# RK3566_OSC_PLL_PMUO1_2.net
KiCad netlist of a schematic drawn in Altium Designer
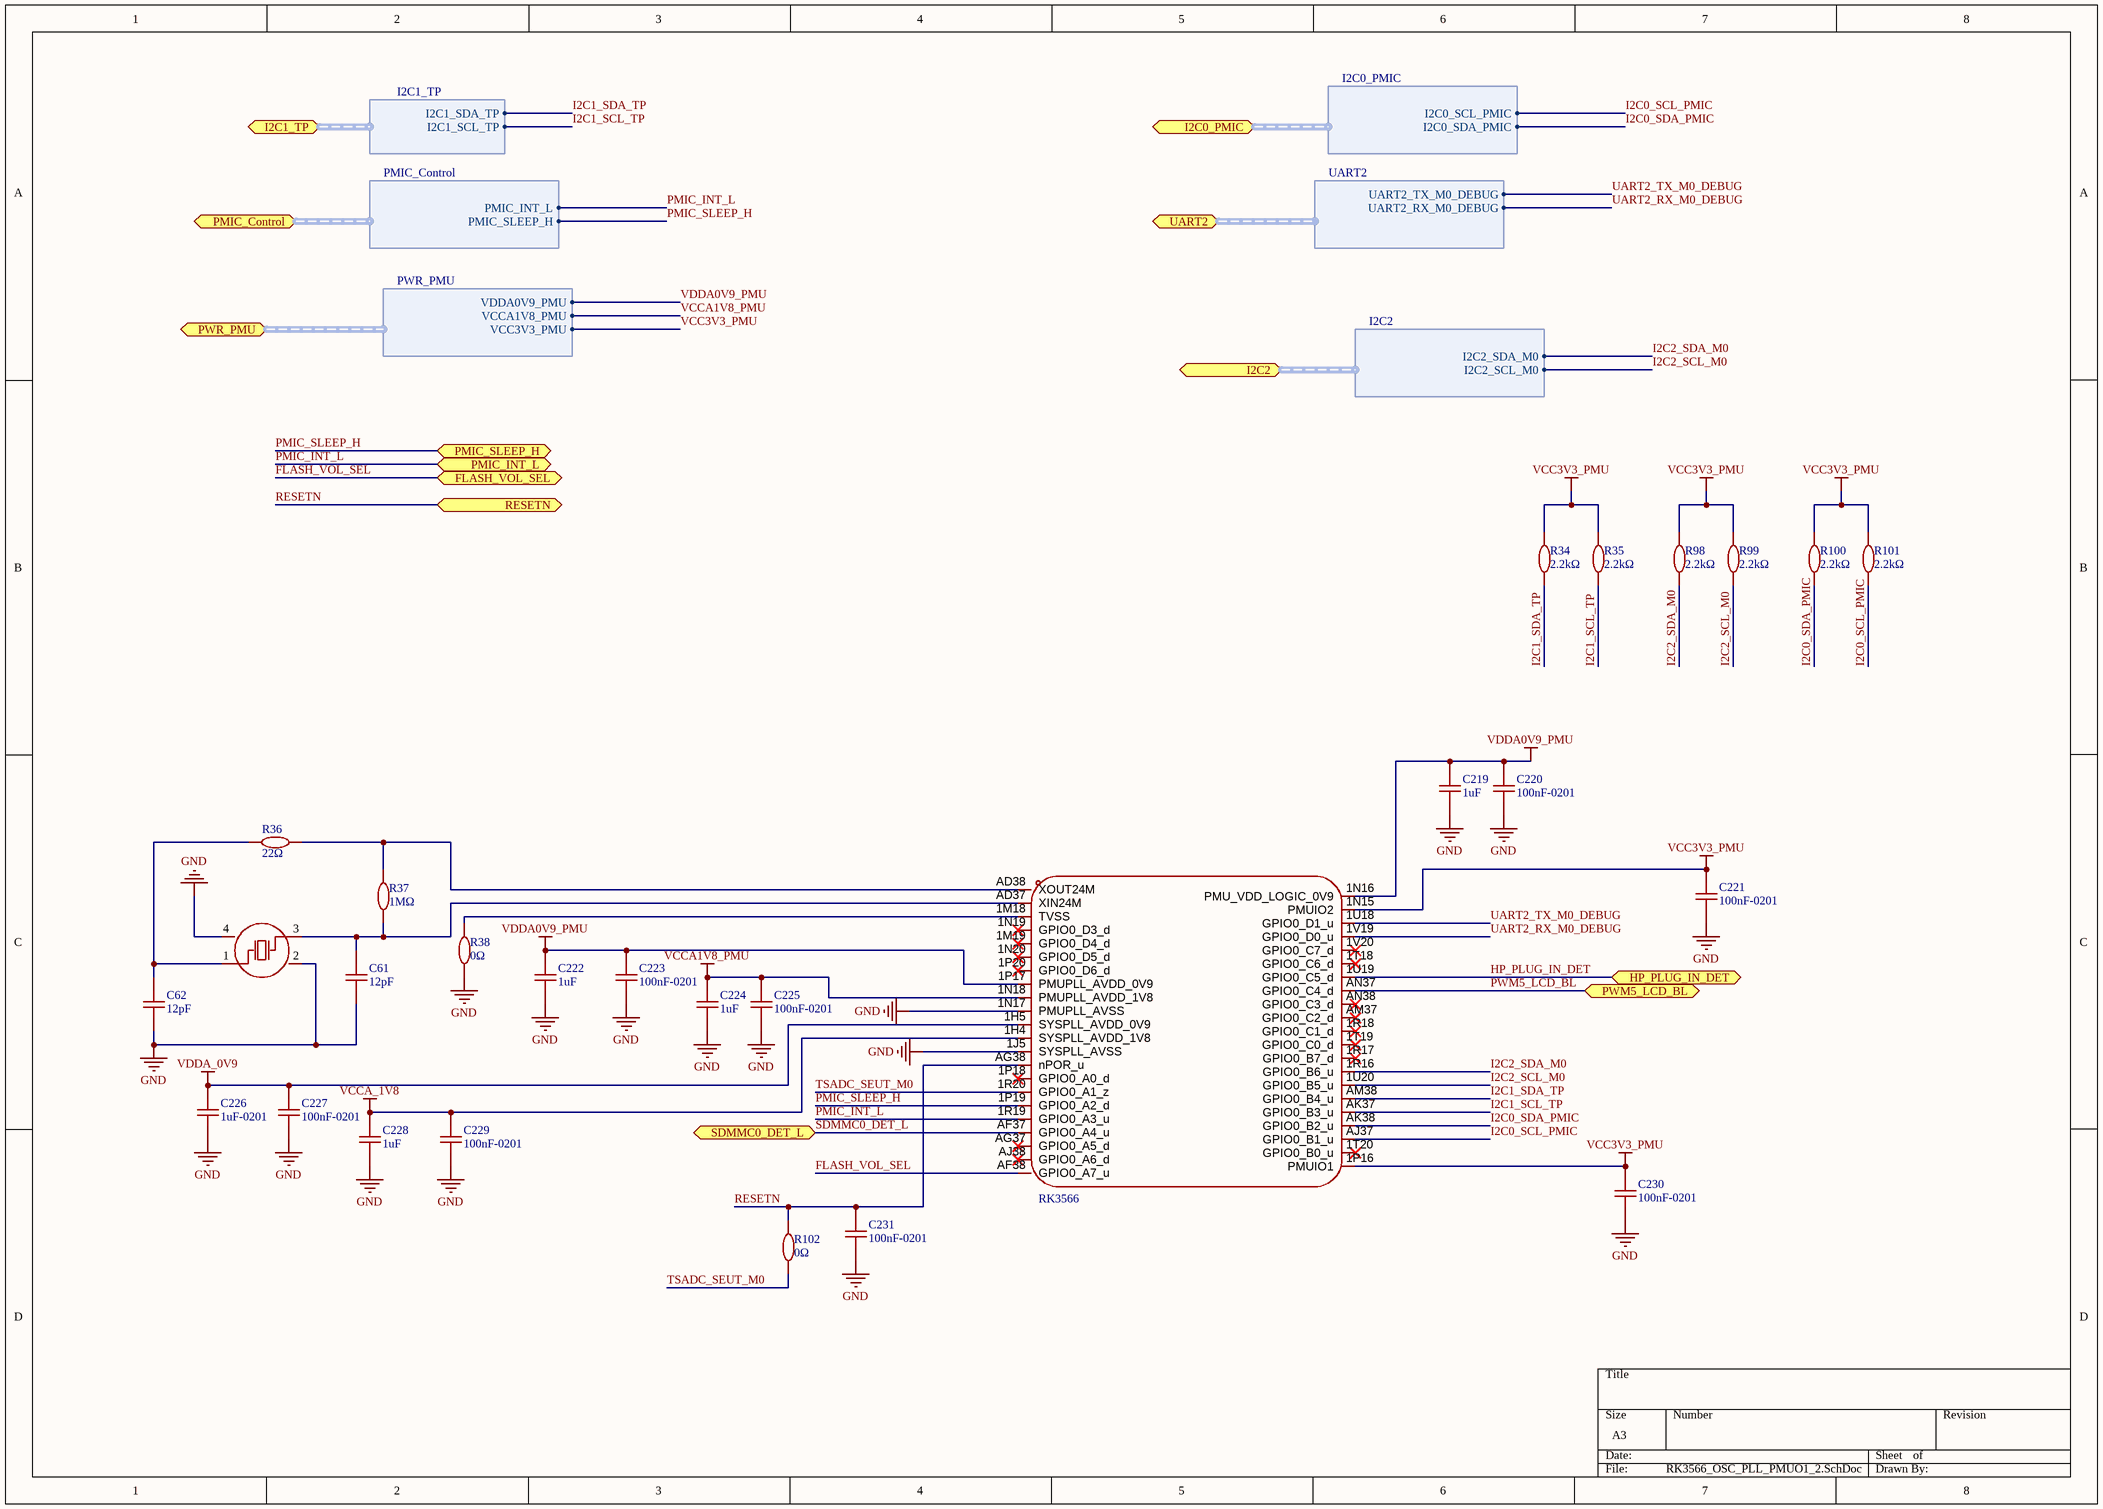
[diagram p0: RK3566_OSC_PLL_PMUO1_2.SchDoc]

(export (version "E")
  (design (tool "Eeschema 10.0.6"))
  (components
    (comp (ref "C61")
      (value "12pF")
      (footprint "C0402")
      (description "50V 12pF C0G ±5% 0402 Ceramic Capacitors ROHS")
      (libsource (lib "RLC") (part "12pF"))
    )
    (comp (ref "C62")
      (value "12pF")
      (footprint "C0402")
      (description "50V 12pF C0G ±5% 0402 Ceramic Capacitors ROHS")
      (libsource (lib "RLC") (part "12pF"))
    )
    (comp (ref "C219")
      (value "1uF")
      (footprint "C0402")
      (description "50V 1uF X5R ±10% 0402 Ceramic Capacitors ROHS")
      (libsource (lib "RLC") (part "1uF"))
    )
    (comp (ref "C220")
      (value "100nF-0201")
      (footprint "C0201")
      (description "CL03A104KO3NNNC")
      (libsource (lib "RLC") (part "100nF-0201"))
    )
    (comp (ref "C221")
      (value "100nF-0201")
      (footprint "C0201")
      (description "CL03A104KO3NNNC")
      (libsource (lib "RLC") (part "100nF-0201"))
    )
    (comp (ref "C222")
      (value "1uF")
      (footprint "C0402")
      (description "50V 1uF X5R ±10% 0402 Ceramic Capacitors ROHS")
      (libsource (lib "RLC") (part "1uF"))
    )
    (comp (ref "C223")
      (value "100nF-0201")
      (footprint "C0201")
      (description "CL03A104KO3NNNC")
      (libsource (lib "RLC") (part "100nF-0201"))
    )
    (comp (ref "C224")
      (value "1uF")
      (footprint "C0402")
      (description "50V 1uF X5R ±10% 0402 Ceramic Capacitors ROHS")
      (libsource (lib "RLC") (part "1uF"))
    )
    (comp (ref "C225")
      (value "100nF-0201")
      (footprint "C0201")
      (description "CL03A104KO3NNNC")
      (libsource (lib "RLC") (part "100nF-0201"))
    )
    (comp (ref "C226")
      (value "1uF-0201")
      (footprint "C0201")
      (description "CL03A104KO3NNNC")
      (libsource (lib "RLC") (part "1uF-0201"))
    )
    (comp (ref "C227")
      (value "100nF-0201")
      (footprint "C0201")
      (description "CL03A104KO3NNNC")
      (libsource (lib "RLC") (part "100nF-0201"))
    )
    (comp (ref "C228")
      (value "1uF")
      (footprint "C0402")
      (description "50V 1uF X5R ±10% 0402 Ceramic Capacitors ROHS")
      (libsource (lib "RLC") (part "1uF"))
    )
    (comp (ref "C229")
      (value "100nF-0201")
      (footprint "C0201")
      (description "CL03A104KO3NNNC")
      (libsource (lib "RLC") (part "100nF-0201"))
    )
    (comp (ref "C230")
      (value "100nF-0201")
      (footprint "C0201")
      (description "CL03A104KO3NNNC")
      (libsource (lib "RLC") (part "100nF-0201"))
    )
    (comp (ref "C231")
      (value "100nF-0201")
      (footprint "C0201")
      (description "CL03A104KO3NNNC")
      (libsource (lib "RLC") (part "100nF-0201"))
    )
    (comp (ref "R34")
      (value "2.2kΩ")
      (footprint "R0402")
      (description "2.2kΩ ±1% 62.5mW 厚膜电阻")
      (libsource (lib "RLC") (part "2.2kΩ"))
    )
    (comp (ref "R35")
      (value "2.2kΩ")
      (footprint "R0402")
      (description "2.2kΩ ±1% 62.5mW 厚膜电阻")
      (libsource (lib "RLC") (part "2.2kΩ"))
    )
    (comp (ref "R36")
      (value "22Ω")
      (footprint "R0402")
      (description "小尺寸、重量轻。降低组装成本,与贴片机匹配。适用于波峰焊和回流焊")
      (libsource (lib "RLC") (part "22Ω"))
    )
    (comp (ref "R37")
      (value "1MΩ")
      (footprint "R0402")
      (description "62.5mW 1MΩ 50V ±100ppm/℃ Thick Film Resistor ±1% 0402 Chip Resistor - Surface Mount ROHS")
      (libsource (lib "RLC") (part "1MΩ"))
    )
    (comp (ref "R38")
      (value "0Ω")
      (footprint "R0402")
      (description "小尺寸、重量轻。降低组装成本,与贴片机匹配。适用于波峰焊和回流焊")
      (libsource (lib "RLC") (part "0Ω-0201"))
    )
    (comp (ref "R98")
      (value "2.2kΩ")
      (footprint "R0402")
      (description "2.2kΩ ±1% 62.5mW 厚膜电阻")
      (libsource (lib "RLC") (part "2.2kΩ"))
    )
    (comp (ref "R99")
      (value "2.2kΩ")
      (footprint "R0402")
      (description "2.2kΩ ±1% 62.5mW 厚膜电阻")
      (libsource (lib "RLC") (part "2.2kΩ"))
    )
    (comp (ref "R100")
      (value "2.2kΩ")
      (footprint "R0402")
      (description "2.2kΩ ±1% 62.5mW 厚膜电阻")
      (libsource (lib "RLC") (part "2.2kΩ"))
    )
    (comp (ref "R101")
      (value "2.2kΩ")
      (footprint "R0402")
      (description "2.2kΩ ±1% 62.5mW 厚膜电阻")
      (libsource (lib "RLC") (part "2.2kΩ"))
    )
    (comp (ref "R102")
      (value "0Ω")
      (footprint "R0402")
      (description "0Ω 62.5mW 50V Thick Film Resistor ±1% 0402 Chip Resistor - Surface Mount ROHS")
      (libsource (lib "RLC") (part "0Ω"))
    )
    (comp (ref "U2")
      (value "RK3566")
      (footprint "BGA-565_L15.5-W14.4-P0.40_RK3566_1")
      (description "BGA-565(15.5x14.4)")
      (libsource (lib "IC") (part "RK3566"))
    )
    (comp (ref "X2")
      (value "24MHz")
      (footprint "CRYSTAL-SMD_4P-L3.2-W2.5-BL")
      (description "Crystal Oscillator 12pF SMD3225-4P Crystals ROHS")
      (fields (field (name "MANUFACTURER") "YXC(扬兴晶振)") (field (name "MANUFACTURER PART") "X322524MOB4SI"))
      (libsource (lib "OSC") (part "X322524MOB4SI"))
    )
  )
  (nets
    (net (code "7") (name "/FLASH_VOL_SEL") (class "Default")
      (node (ref "U2") (pin "AF38") (pinfunction "GPIO0_A7_u_AF38") (pintype "passive"))
    )
    (net (code "8") (name "/HP_PLUG_IN_DET") (class "Default")
      (node (ref "U2") (pin "1U19") (pinfunction "GPIO0_C5_d_1U19") (pintype "passive"))
    )
    (net (code "9") (name "/I2C0_SCL_PMIC") (class "Default")
      (node (ref "R101") (pin "1") (pinfunction "1_1") (pintype "passive"))
      (node (ref "U2") (pin "AJ37") (pinfunction "GPIO0_B1_u_AJ37") (pintype "passive"))
    )
    (net (code "10") (name "/I2C0_SDA_PMIC") (class "Default")
      (node (ref "R100") (pin "1") (pinfunction "1_1") (pintype "passive"))
      (node (ref "U2") (pin "AK38") (pinfunction "GPIO0_B2_u_AK38") (pintype "passive"))
    )
    (net (code "11") (name "/I2C1_SCL_TP") (class "Default")
      (node (ref "R35") (pin "1") (pinfunction "1_1") (pintype "passive"))
      (node (ref "U2") (pin "AK37") (pinfunction "GPIO0_B3_u_AK37") (pintype "passive"))
    )
    (net (code "12") (name "/I2C1_SDA_TP") (class "Default")
      (node (ref "R34") (pin "1") (pinfunction "1_1") (pintype "passive"))
      (node (ref "U2") (pin "AM38") (pinfunction "GPIO0_B4_u_AM38") (pintype "passive"))
    )
    (net (code "13") (name "/I2C2_SCL_M0") (class "Default")
      (node (ref "R99") (pin "1") (pinfunction "1_1") (pintype "passive"))
      (node (ref "U2") (pin "1U20") (pinfunction "GPIO0_B5_u_1U20") (pintype "passive"))
    )
    (net (code "14") (name "/I2C2_SDA_M0") (class "Default")
      (node (ref "R98") (pin "1") (pinfunction "1_1") (pintype "passive"))
      (node (ref "U2") (pin "1R16") (pinfunction "GPIO0_B6_u_1R16") (pintype "passive"))
    )
    (net (code "15") (name "/PMIC_INT_L") (class "Default")
      (node (ref "U2") (pin "1R19") (pinfunction "GPIO0_A3_u_1R19") (pintype "passive"))
    )
    (net (code "16") (name "/PMIC_SLEEP_H") (class "Default")
      (node (ref "U2") (pin "1P19") (pinfunction "GPIO0_A2_d_1P19") (pintype "passive"))
    )
    (net (code "17") (name "/PWM5_LCD_BL") (class "Default")
      (node (ref "U2") (pin "AN37") (pinfunction "GPIO0_C4_d_AN37") (pintype "passive"))
    )
    (net (code "18") (name "/RESETN") (class "Default")
      (node (ref "C231") (pin "2") (pinfunction "2_2") (pintype "passive"))
      (node (ref "R102") (pin "2") (pinfunction "2_2") (pintype "passive"))
      (node (ref "U2") (pin "AG38") (pinfunction "nPOR_u_AG38") (pintype "passive"))
    )
    (net (code "19") (name "/SDMMC0_DET_L") (class "Default")
      (node (ref "U2") (pin "AF37") (pinfunction "GPIO0_A4_u_AF37") (pintype "passive"))
    )
    (net (code "20") (name "/TSADC_SEUT_M0") (class "Default")
      (node (ref "R102") (pin "1") (pinfunction "1_1") (pintype "passive"))
      (node (ref "U2") (pin "1R20") (pinfunction "GPIO0_A1_z_1R20") (pintype "passive"))
    )
    (net (code "21") (name "/UART2_RX_M0_DEBUG") (class "Default")
      (node (ref "U2") (pin "1V19") (pinfunction "GPIO0_D0_u_1V19") (pintype "passive"))
    )
    (net (code "22") (name "/UART2_TX_M0_DEBUG") (class "Default")
      (node (ref "U2") (pin "1U18") (pinfunction "GPIO0_D1_u_1U18") (pintype "passive"))
    )
    (net (code "29") (name "GND") (class "Default")
      (node (ref "C219") (pin "1") (pinfunction "1_1") (pintype "passive"))
      (node (ref "C220") (pin "1") (pinfunction "1_1") (pintype "passive"))
      (node (ref "C221") (pin "1") (pinfunction "1_1") (pintype "passive"))
      (node (ref "C222") (pin "1") (pinfunction "1_1") (pintype "passive"))
      (node (ref "C223") (pin "1") (pinfunction "1_1") (pintype "passive"))
      (node (ref "C224") (pin "1") (pinfunction "1_1") (pintype "passive"))
      (node (ref "C225") (pin "1") (pinfunction "1_1") (pintype "passive"))
      (node (ref "C226") (pin "1") (pinfunction "1_1") (pintype "passive"))
      (node (ref "C227") (pin "1") (pinfunction "1_1") (pintype "passive"))
      (node (ref "C228") (pin "1") (pinfunction "1_1") (pintype "passive"))
      (node (ref "C229") (pin "1") (pinfunction "1_1") (pintype "passive"))
      (node (ref "C230") (pin "1") (pinfunction "1_1") (pintype "passive"))
      (node (ref "C231") (pin "1") (pinfunction "1_1") (pintype "passive"))
      (node (ref "C61") (pin "1") (pinfunction "1_1") (pintype "passive"))
      (node (ref "C62") (pin "1") (pinfunction "1_1") (pintype "passive"))
      (node (ref "R38") (pin "1") (pinfunction "1_1") (pintype "passive"))
      (node (ref "U2") (pin "1J5") (pinfunction "SYSPLL_AVSS_1J5") (pintype "passive"))
      (node (ref "U2") (pin "1N17") (pinfunction "PMUPLL_AVSS_1N17") (pintype "passive"))
      (node (ref "X2") (pin "2") (pinfunction "GND_2") (pintype "passive"))
      (node (ref "X2") (pin "4") (pinfunction "GND_4") (pintype "passive"))
    )
    (net (code "30") (name "Net-(U2D-TVSS)") (class "Default")
      (node (ref "R38") (pin "2") (pinfunction "2_2") (pintype "passive"))
      (node (ref "U2") (pin "1M18") (pinfunction "TVSS_1M18") (pintype "passive"))
    )
    (net (code "31") (name "Net-(U2D-XIN24M)") (class "Default")
      (node (ref "C61") (pin "2") (pinfunction "2_2") (pintype "passive"))
      (node (ref "R37") (pin "1") (pinfunction "1_1") (pintype "passive"))
      (node (ref "U2") (pin "AD37") (pinfunction "XIN24M_AD37") (pintype "passive"))
      (node (ref "X2") (pin "3") (pinfunction "OSC2_3") (pintype "passive"))
    )
    (net (code "32") (name "Net-(U2D-XOUT24M)") (class "Default")
      (node (ref "R36") (pin "2") (pinfunction "2_2") (pintype "passive"))
      (node (ref "R37") (pin "2") (pinfunction "2_2") (pintype "passive"))
      (node (ref "U2") (pin "AD38") (pinfunction "XOUT24M_AD38") (pintype "passive"))
    )
    (net (code "33") (name "Net-(X2-OSC1)") (class "Default")
      (node (ref "C62") (pin "2") (pinfunction "2_2") (pintype "passive"))
      (node (ref "R36") (pin "1") (pinfunction "1_1") (pintype "passive"))
      (node (ref "X2") (pin "1") (pinfunction "OSC1_1") (pintype "passive"))
    )
    (net (code "34") (name "VCC3V3_PMU") (class "Default")
      (node (ref "C221") (pin "2") (pinfunction "2_2") (pintype "passive"))
      (node (ref "C230") (pin "2") (pinfunction "2_2") (pintype "passive"))
      (node (ref "R100") (pin "2") (pinfunction "2_2") (pintype "passive"))
      (node (ref "R101") (pin "2") (pinfunction "2_2") (pintype "passive"))
      (node (ref "R34") (pin "2") (pinfunction "2_2") (pintype "passive"))
      (node (ref "R35") (pin "2") (pinfunction "2_2") (pintype "passive"))
      (node (ref "R98") (pin "2") (pinfunction "2_2") (pintype "passive"))
      (node (ref "R99") (pin "2") (pinfunction "2_2") (pintype "passive"))
      (node (ref "U2") (pin "1N15") (pinfunction "PMUIO2_1N15") (pintype "passive"))
      (node (ref "U2") (pin "1P16") (pinfunction "PMUIO1_1P16") (pintype "passive"))
    )
    (net (code "35") (name "VCCA1V8_PMU") (class "Default")
      (node (ref "C224") (pin "2") (pinfunction "2_2") (pintype "passive"))
      (node (ref "C225") (pin "2") (pinfunction "2_2") (pintype "passive"))
      (node (ref "U2") (pin "1N18") (pinfunction "PMUPLL_AVDD_1V8_1N18") (pintype "passive"))
    )
    (net (code "36") (name "VCCA_1V8") (class "Default")
      (node (ref "C228") (pin "2") (pinfunction "2_2") (pintype "passive"))
      (node (ref "C229") (pin "2") (pinfunction "2_2") (pintype "passive"))
      (node (ref "U2") (pin "1H4") (pinfunction "SYSPLL_AVDD_1V8_1H4") (pintype "passive"))
    )
    (net (code "37") (name "VDDA0V9_PMU") (class "Default")
      (node (ref "C219") (pin "2") (pinfunction "2_2") (pintype "passive"))
      (node (ref "C220") (pin "2") (pinfunction "2_2") (pintype "passive"))
      (node (ref "C222") (pin "2") (pinfunction "2_2") (pintype "passive"))
      (node (ref "C223") (pin "2") (pinfunction "2_2") (pintype "passive"))
      (node (ref "U2") (pin "1N16") (pinfunction "PMU_VDD_LOGIC_0V9_1N16") (pintype "passive"))
      (node (ref "U2") (pin "1P17") (pinfunction "PMUPLL_AVDD_0V9_1P17") (pintype "passive"))
    )
    (net (code "38") (name "VDDA_0V9") (class "Default")
      (node (ref "C226") (pin "2") (pinfunction "2_2") (pintype "passive"))
      (node (ref "C227") (pin "2") (pinfunction "2_2") (pintype "passive"))
      (node (ref "U2") (pin "1H5") (pinfunction "SYSPLL_AVDD_0V9_1H5") (pintype "passive"))
    )
    (net (code "39") (name "unconnected-(U2D-GPIO0_A0_d-Pad1P18)") (class "Default")
      (node (ref "U2") (pin "1P18") (pinfunction "GPIO0_A0_d_1P18") (pintype "passive+no_connect"))
    )
    (net (code "40") (name "unconnected-(U2D-GPIO0_A5_d-PadAG37)") (class "Default")
      (node (ref "U2") (pin "AG37") (pinfunction "GPIO0_A5_d_AG37") (pintype "passive+no_connect"))
    )
    (net (code "41") (name "unconnected-(U2D-GPIO0_A6_d-PadAJ38)") (class "Default")
      (node (ref "U2") (pin "AJ38") (pinfunction "GPIO0_A6_d_AJ38") (pintype "passive+no_connect"))
    )
    (net (code "42") (name "unconnected-(U2D-GPIO0_B0_u-Pad1T20)") (class "Default")
      (node (ref "U2") (pin "1T20") (pinfunction "GPIO0_B0_u_1T20") (pintype "passive+no_connect"))
    )
    (net (code "43") (name "unconnected-(U2D-GPIO0_B7_d-Pad1R17)") (class "Default")
      (node (ref "U2") (pin "1R17") (pinfunction "GPIO0_B7_d_1R17") (pintype "passive+no_connect"))
    )
    (net (code "44") (name "unconnected-(U2D-GPIO0_C0_d-Pad1T19)") (class "Default")
      (node (ref "U2") (pin "1T19") (pinfunction "GPIO0_C0_d_1T19") (pintype "passive+no_connect"))
    )
    (net (code "45") (name "unconnected-(U2D-GPIO0_C1_d-Pad1R18)") (class "Default")
      (node (ref "U2") (pin "1R18") (pinfunction "GPIO0_C1_d_1R18") (pintype "passive+no_connect"))
    )
    (net (code "46") (name "unconnected-(U2D-GPIO0_C2_d-PadAM37)") (class "Default")
      (node (ref "U2") (pin "AM37") (pinfunction "GPIO0_C2_d_AM37") (pintype "passive+no_connect"))
    )
    (net (code "47") (name "unconnected-(U2D-GPIO0_C3_d-PadAN38)") (class "Default")
      (node (ref "U2") (pin "AN38") (pinfunction "GPIO0_C3_d_AN38") (pintype "passive+no_connect"))
    )
    (net (code "48") (name "unconnected-(U2D-GPIO0_C6_d-Pad1T18)") (class "Default")
      (node (ref "U2") (pin "1T18") (pinfunction "GPIO0_C6_d_1T18") (pintype "passive+no_connect"))
    )
    (net (code "49") (name "unconnected-(U2D-GPIO0_C7_d-Pad1V20)") (class "Default")
      (node (ref "U2") (pin "1V20") (pinfunction "GPIO0_C7_d_1V20") (pintype "passive+no_connect"))
    )
    (net (code "50") (name "unconnected-(U2D-GPIO0_D3_d-Pad1N19)") (class "Default")
      (node (ref "U2") (pin "1N19") (pinfunction "GPIO0_D3_d_1N19") (pintype "passive+no_connect"))
    )
    (net (code "51") (name "unconnected-(U2D-GPIO0_D4_d-Pad1M19)") (class "Default")
      (node (ref "U2") (pin "1M19") (pinfunction "GPIO0_D4_d_1M19") (pintype "passive+no_connect"))
    )
    (net (code "52") (name "unconnected-(U2D-GPIO0_D5_d-Pad1N20)") (class "Default")
      (node (ref "U2") (pin "1N20") (pinfunction "GPIO0_D5_d_1N20") (pintype "passive+no_connect"))
    )
    (net (code "53") (name "unconnected-(U2D-GPIO0_D6_d-Pad1P20)") (class "Default")
      (node (ref "U2") (pin "1P20") (pinfunction "GPIO0_D6_d_1P20") (pintype "passive+no_connect"))
    )
  )
)
